# transcievers.net
KiCad netlist of a schematic drawn in Altium Designer
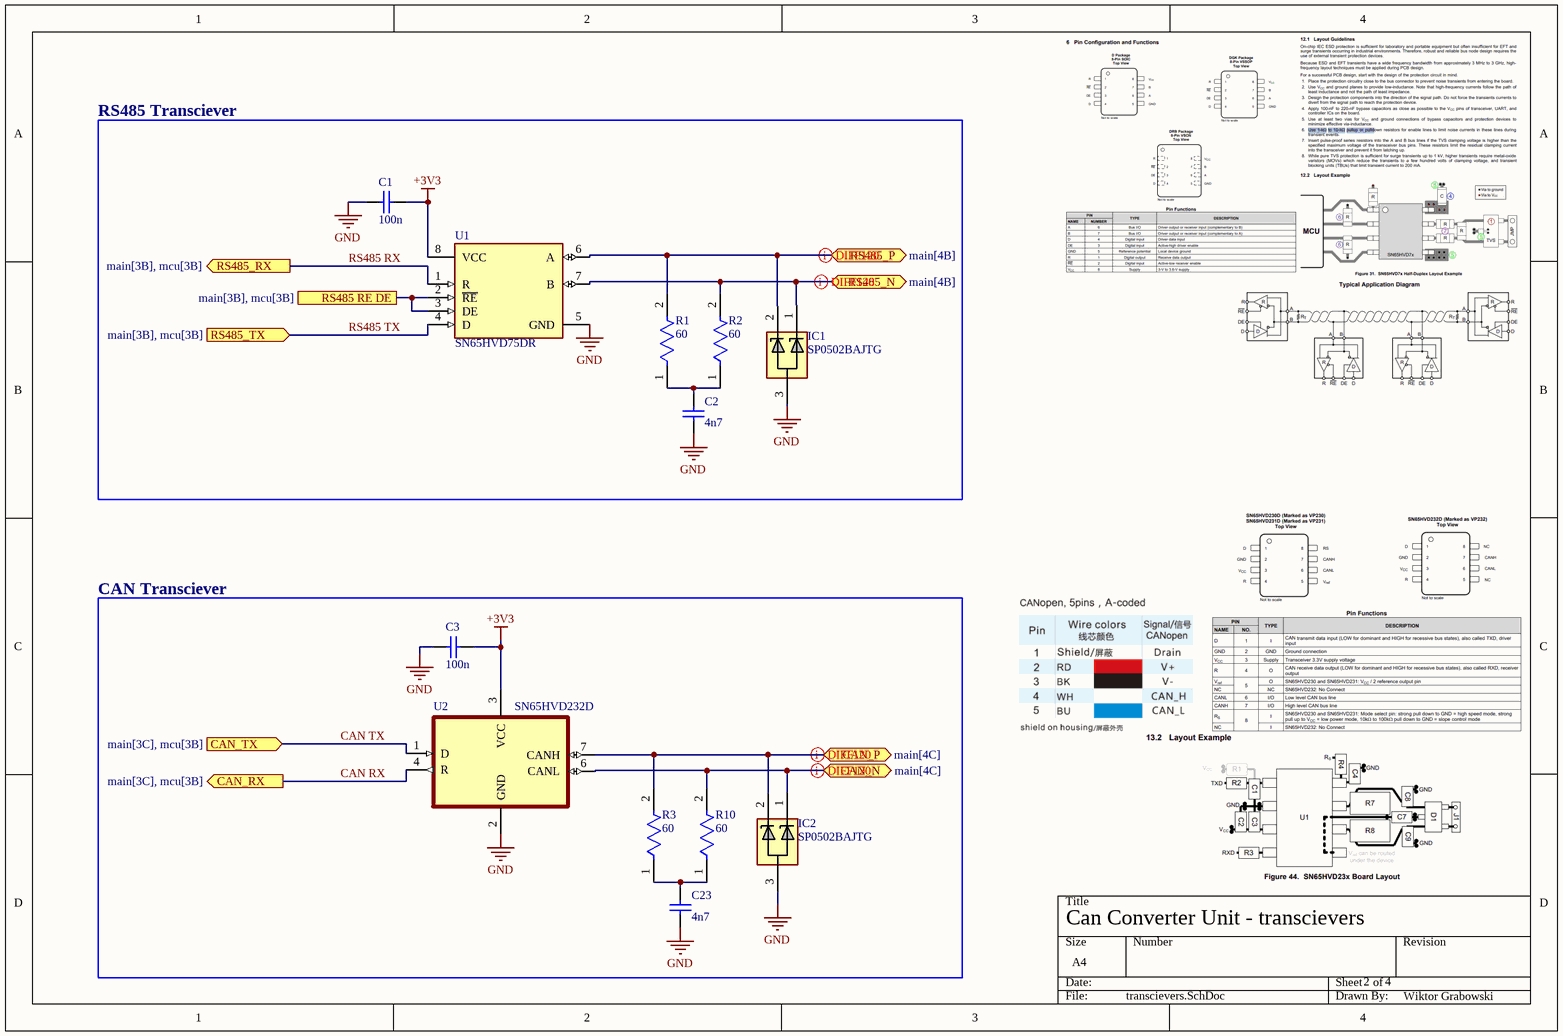
[diagram p0: transcievers.SchDoc]

(export (version "E")
  (design (tool "Eeschema 10.0.6"))
  (components
    (comp (ref "C1")
      (value "100n")
      (footprint "CAPC1206(3216)170_M")
      (description "CAP 47nF 200V ±10% 1206 (3216 Metric) Thickness 1.7mm SMD")
      (fields (field (name "TOLERANCE") "Â±10%"))
      (libsource (lib "Altium Content Vault") (part "CAP"))
    )
    (comp (ref "C2")
      (value "4n7")
      (footprint "CAPC1206(3216)150_L")
      (description "CAP 1.8uF 10V ±5% 1206 (3216 Metric) Thickness 1.45mm SMD")
      (fields (field (name "TOLERANCE") "Â±5%"))
      (libsource (lib "Altium Content Vault") (part "CAP"))
    )
    (comp (ref "C3")
      (value "100n")
      (footprint "CAPC1206(3216)170_M")
      (description "CAP 47nF 200V ±10% 1206 (3216 Metric) Thickness 1.7mm SMD")
      (fields (field (name "TOLERANCE") "Â±10%"))
      (libsource (lib "Altium Content Vault") (part "CAP"))
    )
    (comp (ref "C23")
      (value "4n7")
      (footprint "CAPC1206(3216)150_L")
      (description "CAP 1.8uF 10V ±5% 1206 (3216 Metric) Thickness 1.45mm SMD")
      (fields (field (name "TOLERANCE") "Â±5%"))
      (libsource (lib "Altium Content Vault") (part "CAP"))
    )
    (comp (ref "IC1")
      (value "SP0502BAJTG")
      (footprint "SOT132P220X110-3N")
      (description "Integrated Circuit")
      (fields (field (name "MOUSER PART NUMBER") "576-SP0502BAJTG"))
      (libsource (lib "HydrogreenLibrary") (part "SP0502BAJTG"))
    )
    (comp (ref "IC2")
      (value "SP0502BAJTG")
      (footprint "SOT132P220X110-3N")
      (description "Integrated Circuit")
      (fields (field (name "MOUSER PART NUMBER") "576-SP0502BAJTG"))
      (libsource (lib "HydrogreenLibrary") (part "SP0502BAJTG"))
    )
    (comp (ref "R1")
      (value "60")
      (footprint "FP-RK73H2B-MFG")
      (description "40.2kΩ ±1% 0.25W Chip Resistor 1206 Thick Film AEC-Q200 Qualified")
      (fields (field (name "TOLERANCE") "1%"))
      (libsource (lib "Altium Content Vault") (part "1029c3af85768c4190bb7ad29bc67b5"))
    )
    (comp (ref "R2")
      (value "60")
      (footprint "FP-RK73H2B-MFG")
      (description "40.2kΩ ±1% 0.25W Chip Resistor 1206 Thick Film AEC-Q200 Qualified")
      (fields (field (name "TOLERANCE") "1%"))
      (libsource (lib "Altium Content Vault") (part "1029c3af85768c4190bb7ad29bc67b5"))
    )
    (comp (ref "R3")
      (value "60")
      (footprint "FP-RK73H2B-MFG")
      (description "40.2kΩ ±1% 0.25W Chip Resistor 1206 Thick Film AEC-Q200 Qualified")
      (fields (field (name "TOLERANCE") "1%"))
      (libsource (lib "Altium Content Vault") (part "1029c3af85768c4190bb7ad29bc67b5"))
    )
    (comp (ref "R10")
      (value "60")
      (footprint "FP-RK73H2B-MFG")
      (description "40.2kΩ ±1% 0.25W Chip Resistor 1206 Thick Film AEC-Q200 Qualified")
      (fields (field (name "TOLERANCE") "1%"))
      (libsource (lib "Altium Content Vault") (part "1029c3af85768c4190bb7ad29bc67b5"))
    )
    (comp (ref "U1")
      (value "SN65HVD75DR")
      (footprint "SN65HVD75DR")
      (description "Single Transmitter/Receiver RS-422/RS-485 8-Pin SOIC T/R")
      (fields (field (name "MANUFACTURER") "Texas Instruments"))
      (libsource (lib "HydrogreenLibrary") (part "SN65HVD75DR"))
    )
    (comp (ref "U2")
      (value "SN65HVD232D")
      (footprint "SN65HVD232D")
      (description "Texas Instruments - SN65HVD232DR - Can Transceiver, 1MBPS, 1/1, 3.3V, SOIC-8, Full Reel")
      (fields
        (field (name "MF") "Texas Instruments")
        (field (name "MANUFACTURER PART NUMBER") "SN65HVD232DR")
      )
      (libsource (lib "HydrogreenLibrary") (part "SN65HVD232D"))
    )
  )
  (nets
    (net (code "1") (name "+3V3") (class "Default")
      (node (ref "C1") (pin "1") (pinfunction "1_1") (pintype "passive"))
      (node (ref "C3") (pin "1") (pinfunction "1_1") (pintype "passive"))
      (node (ref "U1") (pin "8") (pinfunction "VCC_8") (pintype "power_in"))
      (node (ref "U2") (pin "3") (pinfunction "VCC_3") (pintype "power_in"))
    )
    (net (code "2") (name "/CAN RX") (class "Default")
      (node (ref "U2") (pin "4") (pinfunction "R_4") (pintype "output"))
    )
    (net (code "3") (name "/CAN TX") (class "Default")
      (node (ref "U2") (pin "1") (pinfunction "D_1") (pintype "input"))
    )
    (net (code "4") (name "/CAN_N") (class "Default")
      (node (ref "IC2") (pin "1") (pintype "passive"))
      (node (ref "R10") (pin "2") (pinfunction "2_2") (pintype "passive"))
      (node (ref "U2") (pin "6") (pinfunction "CANL_6") (pintype "bidirectional"))
    )
    (net (code "5") (name "/CAN_P") (class "Default")
      (node (ref "IC2") (pin "2") (pintype "passive"))
      (node (ref "R3") (pin "2") (pinfunction "2_2") (pintype "passive"))
      (node (ref "U2") (pin "7") (pinfunction "CANH_7") (pintype "bidirectional"))
    )
    (net (code "6") (name "/RS485 RE DE") (class "Default")
      (node (ref "U1") (pin "2") (pinfunction "~{RE}_2") (pintype "input"))
      (node (ref "U1") (pin "3") (pinfunction "DE_3") (pintype "input"))
    )
    (net (code "7") (name "/RS485 RX") (class "Default")
      (node (ref "U1") (pin "1") (pinfunction "R_1") (pintype "input"))
    )
    (net (code "8") (name "/RS485 TX") (class "Default")
      (node (ref "U1") (pin "4") (pinfunction "D_4") (pintype "input"))
    )
    (net (code "9") (name "/RS485_N") (class "Default")
      (node (ref "IC1") (pin "1") (pintype "passive"))
      (node (ref "R2") (pin "2") (pinfunction "2_2") (pintype "passive"))
      (node (ref "U1") (pin "7") (pinfunction "B_7") (pintype "bidirectional"))
    )
    (net (code "10") (name "/RS485_P") (class "Default")
      (node (ref "IC1") (pin "2") (pintype "passive"))
      (node (ref "R1") (pin "2") (pinfunction "2_2") (pintype "passive"))
      (node (ref "U1") (pin "6") (pinfunction "A_6") (pintype "bidirectional"))
    )
    (net (code "11") (name "GND") (class "Default")
      (node (ref "C1") (pin "2") (pinfunction "2_2") (pintype "passive"))
      (node (ref "C2") (pin "2") (pinfunction "2_2") (pintype "passive"))
      (node (ref "C23") (pin "2") (pinfunction "2_2") (pintype "passive"))
      (node (ref "C3") (pin "2") (pinfunction "2_2") (pintype "passive"))
      (node (ref "IC1") (pin "3") (pintype "passive"))
      (node (ref "IC2") (pin "3") (pintype "passive"))
      (node (ref "U1") (pin "5") (pinfunction "GND_5") (pintype "power_in"))
      (node (ref "U2") (pin "2") (pinfunction "GND_2") (pintype "power_in"))
    )
    (net (code "12") (name "Net-(C2-Pad1)") (class "Default")
      (node (ref "C2") (pin "1") (pinfunction "1_1") (pintype "passive"))
      (node (ref "R1") (pin "1") (pinfunction "1_1") (pintype "passive"))
      (node (ref "R2") (pin "1") (pinfunction "1_1") (pintype "passive"))
    )
    (net (code "13") (name "Net-(C23-Pad1)") (class "Default")
      (node (ref "C23") (pin "1") (pinfunction "1_1") (pintype "passive"))
      (node (ref "R10") (pin "1") (pinfunction "1_1") (pintype "passive"))
      (node (ref "R3") (pin "1") (pinfunction "1_1") (pintype "passive"))
    )
  )
)
